# Awesome-Shield-0_6.net
KiCad netlist of a schematic drawn in EAGLE
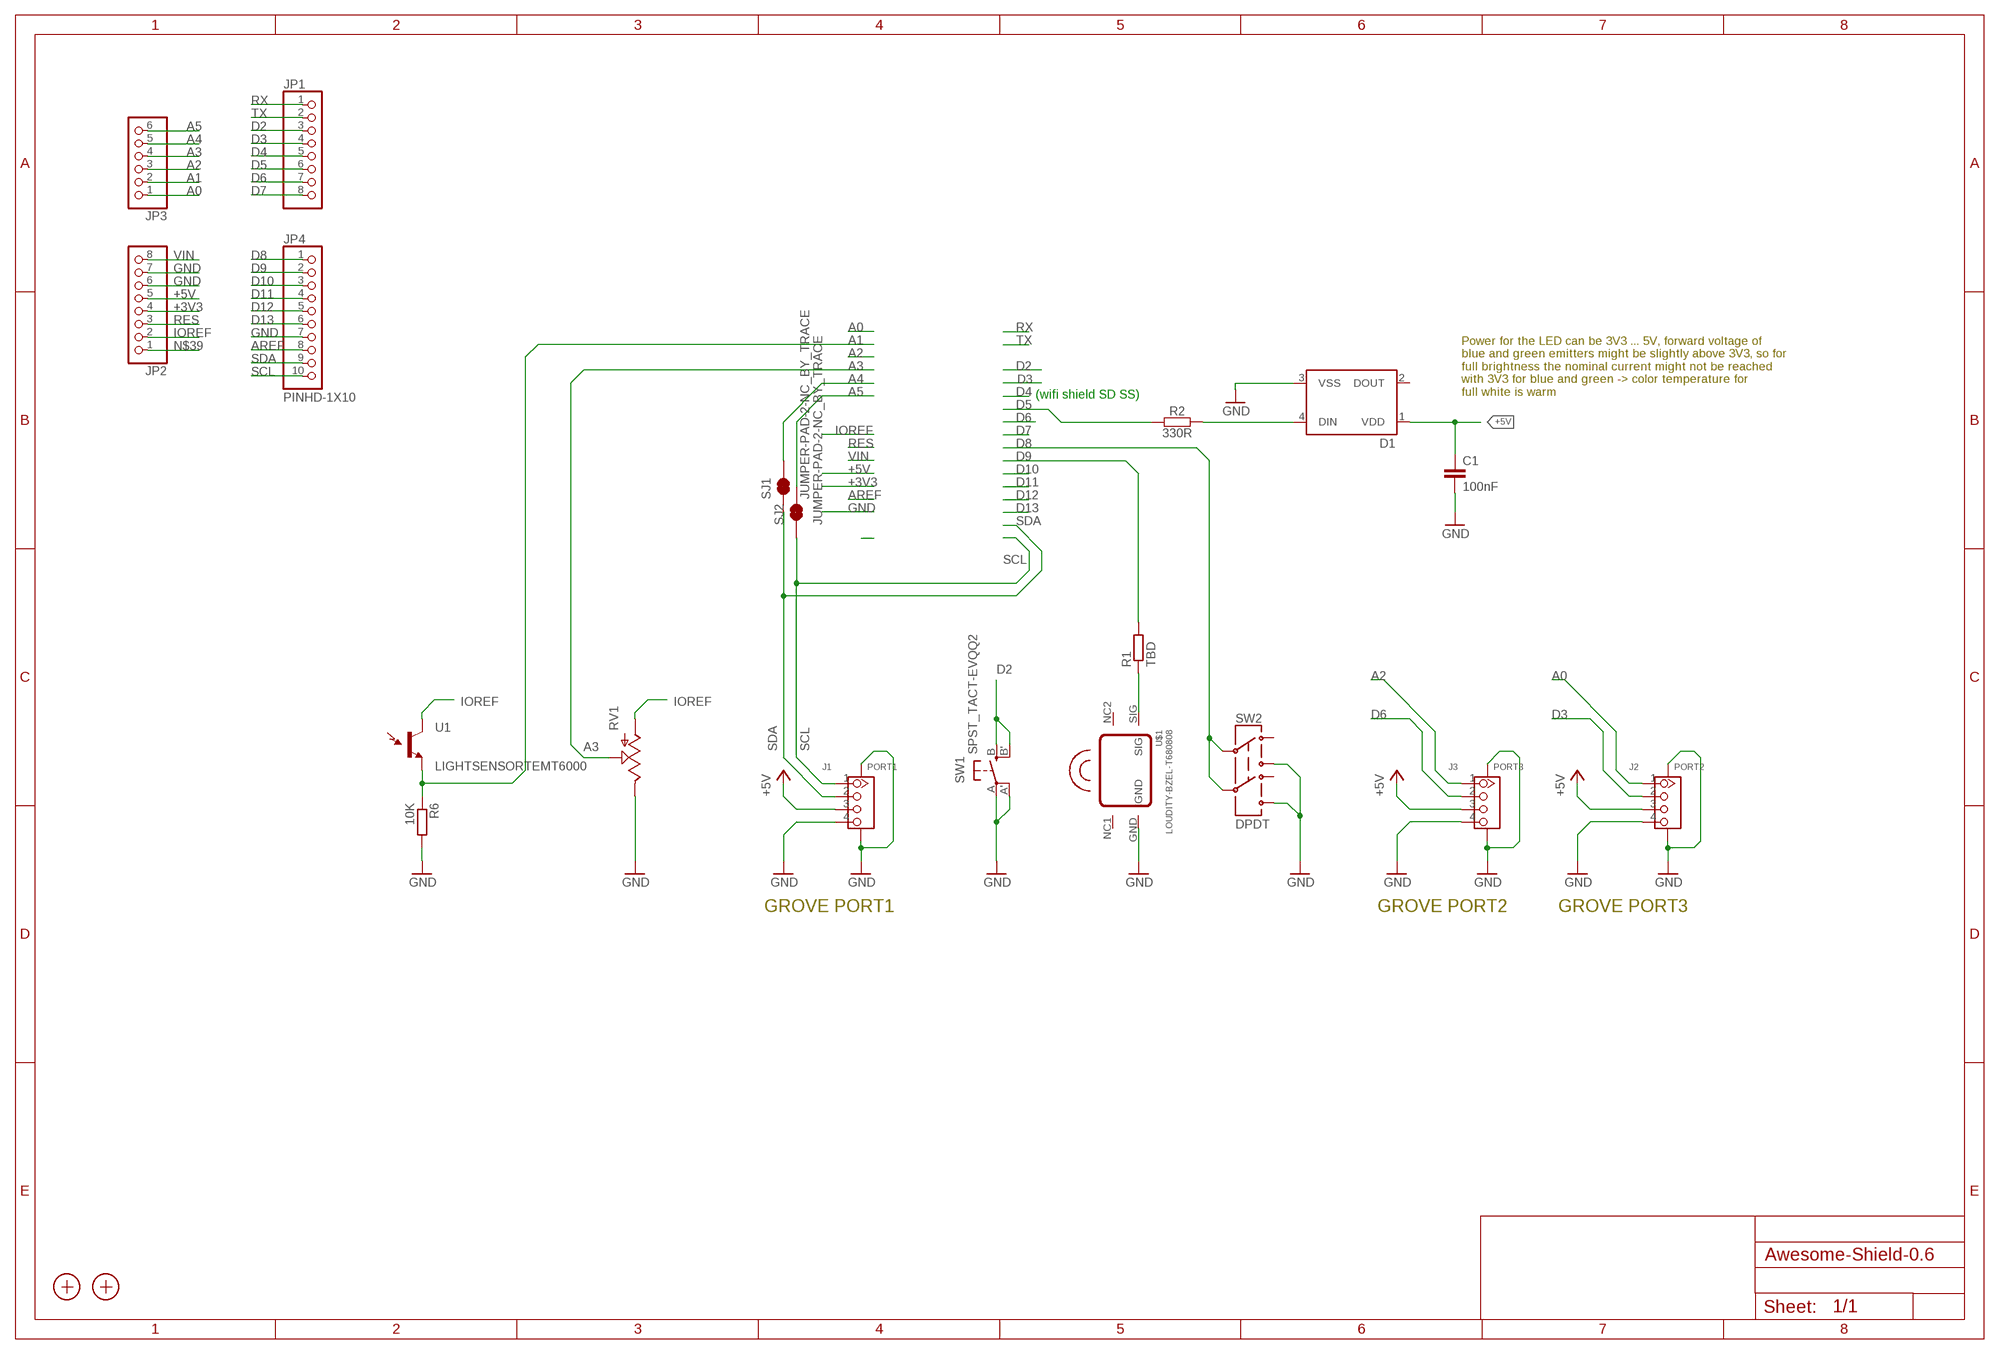
[diagram p0: schematic, sheet 1]

(export (version "E")
  (design (tool "Eeschema 10.0.6"))
  (components
    (comp (ref "C1")
      (value "100nF")
      (footprint "eagle-import:C0603")
      (libsource (lib "eagle-import") (part "C-EUC0603"))
    )
    (comp (ref "D1")
      (value "WS2812B")
      (footprint "eagle-import:WS2812B")
      (libsource (lib "eagle-import") (part "WS2812B"))
    )
    (comp (ref "J1")
      (value "PORT1")
      (footprint "eagle-import:HW4-SMD-2.0")
      (libsource (lib "eagle-import") (part "GROVE-CONNECTOR-SMD(4+2P-2.0)"))
    )
    (comp (ref "J2")
      (value "PORT2")
      (footprint "eagle-import:HW4-SMD-2.0")
      (libsource (lib "eagle-import") (part "GROVE-CONNECTOR-SMD(4+2P-2.0)"))
    )
    (comp (ref "J3")
      (value "PORT3")
      (footprint "eagle-import:HW4-SMD-2.0")
      (libsource (lib "eagle-import") (part "GROVE-CONNECTOR-SMD(4+2P-2.0)"))
    )
    (comp (ref "JP1")
      (value "PINHD-1X8CLEANBIG")
      (footprint "eagle-import:1X08-CLEANBIG")
      (libsource (lib "eagle-import") (part "PINHD-1X8CLEANBIG"))
    )
    (comp (ref "JP2")
      (value "PINHD-1X8CLEANBIG")
      (footprint "eagle-import:1X08-CLEANBIG")
      (libsource (lib "eagle-import") (part "PINHD-1X8CLEANBIG"))
    )
    (comp (ref "JP3")
      (value "PINHD-1X6CLEAN")
      (footprint "eagle-import:1X06-CLEAN")
      (libsource (lib "eagle-import") (part "PINHD-1X6CLEAN"))
    )
    (comp (ref "JP4")
      (value "PINHD-1X10")
      (footprint "eagle-import:1X10-BIG")
      (libsource (lib "eagle-import") (part "PINHD-1X10"))
    )
    (comp (ref "R1")
      (value "TBD")
      (footprint "eagle-import:R1206")
      (libsource (lib "eagle-import") (part "R-EU_R1206"))
    )
    (comp (ref "R2")
      (value "330R")
      (footprint "eagle-import:C1206")
      (libsource (lib "eagle-import") (part "RESISTOR-1206"))
    )
    (comp (ref "R6")
      (value "10K")
      (footprint "eagle-import:R1206")
      (libsource (lib "eagle-import") (part "R-EU_R1206"))
    )
    (comp (ref "RV1")
      (value "POT")
      (footprint "eagle-import:ALPS_POT")
      (libsource (lib "eagle-import") (part "POT"))
    )
    (comp (ref "SJ1")
      (value "JUMPER-PAD-2-NC_BY_TRACE")
      (footprint "eagle-import:PAD-JUMPER-2-NC_BY_TRACE_YES_SILK")
      (libsource (lib "eagle-import") (part "JUMPER-PAD-2-NC_BY_TRACE"))
    )
    (comp (ref "SJ2")
      (value "JUMPER-PAD-2-NC_BY_TRACE")
      (footprint "eagle-import:PAD-JUMPER-2-NC_BY_TRACE_YES_SILK")
      (libsource (lib "eagle-import") (part "JUMPER-PAD-2-NC_BY_TRACE"))
    )
    (comp (ref "SW1")
      (value "SPST_TACT-EVQQ2")
      (footprint "eagle-import:EVQ-Q2")
      (libsource (lib "eagle-import") (part "SPST_TACT-EVQQ2"))
    )
    (comp (ref "SW2")
      (value "DPDT")
      (footprint "eagle-import:AYZ0202")
      (libsource (lib "eagle-import") (part "SWITCH-DPDTAYZ0202"))
    )
    (comp (ref "U$1")
      (value "LOUDITY-BZEL-T680808")
      (footprint "eagle-import:SMT-68")
      (libsource (lib "eagle-import") (part "LOUDITY-BZEL-T680808"))
    )
    (comp (ref "U1")
      (value "LIGHTSENSORTEMT6000")
      (footprint "eagle-import:TEMT6000-SEN")
      (libsource (lib "eagle-import") (part "LIGHTSENSORTEMT6000"))
    )
    (comp (ref "X1")
      (value "PASSER-07")
      (footprint "eagle-import:PASSER_07MM")
      (libsource (lib "eagle-import") (part "PASSER-07"))
    )
    (comp (ref "X2")
      (value "PASSER-07")
      (footprint "eagle-import:PASSER_07MM")
      (libsource (lib "eagle-import") (part "PASSER-07"))
    )
  )
  (nets
    (net (code "1") (name "+5V") (class "Default")
      (node (ref "C1") (pin "1") (pinfunction "1_1") (pintype "passive"))
      (node (ref "D1") (pin "1") (pinfunction "VDD_1") (pintype "power_in"))
      (node (ref "J1") (pin "3") (pinfunction "3_3") (pintype "bidirectional"))
      (node (ref "J2") (pin "3") (pinfunction "3_3") (pintype "bidirectional"))
      (node (ref "J3") (pin "3") (pinfunction "3_3") (pintype "bidirectional"))
      (node (ref "JP2") (pin "5") (pinfunction "5_5") (pintype "passive"))
    )
    (net (code "2") (name "/+3V3") (class "Default")
      (node (ref "JP2") (pin "4") (pinfunction "4_4") (pintype "passive"))
    )
    (net (code "3") (name "/A0") (class "Default")
      (node (ref "J2") (pin "1") (pinfunction "1_1") (pintype "bidirectional"))
      (node (ref "JP3") (pin "1") (pinfunction "1_1") (pintype "passive"))
    )
    (net (code "4") (name "/A1") (class "Default")
      (node (ref "JP3") (pin "2") (pinfunction "2_2") (pintype "passive"))
      (node (ref "R6") (pin "1") (pinfunction "1_1") (pintype "passive"))
      (node (ref "U1") (pin "EMITTER") (pinfunction "E1_EMITTER") (pintype "passive"))
    )
    (net (code "5") (name "/A2") (class "Default")
      (node (ref "J3") (pin "1") (pinfunction "1_1") (pintype "bidirectional"))
      (node (ref "JP3") (pin "3") (pinfunction "3_3") (pintype "passive"))
    )
    (net (code "6") (name "/A3") (class "Default")
      (node (ref "JP3") (pin "4") (pinfunction "4_4") (pintype "passive"))
      (node (ref "RV1") (pin "P$2") (pinfunction "S_P$2") (pintype "passive"))
    )
    (net (code "7") (name "/A4") (class "Default")
      (node (ref "JP3") (pin "5") (pinfunction "5_5") (pintype "passive"))
      (node (ref "SJ1") (pin "2") (pinfunction "2_2") (pintype "passive"))
    )
    (net (code "8") (name "/A5") (class "Default")
      (node (ref "JP3") (pin "6") (pinfunction "6_6") (pintype "passive"))
      (node (ref "SJ2") (pin "2") (pinfunction "2_2") (pintype "passive"))
    )
    (net (code "9") (name "/AREF") (class "Default")
      (node (ref "JP4") (pin "8") (pinfunction "8_8") (pintype "passive"))
    )
    (net (code "10") (name "/D2") (class "Default")
      (node (ref "JP1") (pin "3") (pinfunction "3_3") (pintype "passive"))
      (node (ref "SW1") (pin "B") (pinfunction "S_B") (pintype "passive"))
      (node (ref "SW1") (pin "B'") (pinfunction "S1_B'") (pintype "passive"))
    )
    (net (code "11") (name "/D3") (class "Default")
      (node (ref "J2") (pin "2") (pinfunction "2_2") (pintype "bidirectional"))
      (node (ref "JP1") (pin "4") (pinfunction "4_4") (pintype "passive"))
    )
    (net (code "12") (name "/D4") (class "Default")
      (node (ref "JP1") (pin "5") (pinfunction "5_5") (pintype "passive"))
    )
    (net (code "13") (name "/D5") (class "Default")
      (node (ref "JP1") (pin "6") (pinfunction "6_6") (pintype "passive"))
      (node (ref "R2") (pin "1") (pinfunction "1_1") (pintype "passive"))
    )
    (net (code "14") (name "/D6") (class "Default")
      (node (ref "J3") (pin "2") (pinfunction "2_2") (pintype "bidirectional"))
      (node (ref "JP1") (pin "7") (pinfunction "7_7") (pintype "passive"))
    )
    (net (code "15") (name "/D7") (class "Default")
      (node (ref "JP1") (pin "8") (pinfunction "8_8") (pintype "passive"))
    )
    (net (code "16") (name "/D8") (class "Default")
      (node (ref "JP4") (pin "1") (pinfunction "1_1") (pintype "passive"))
      (node (ref "SW2") (pin "2") (pinfunction "2_2") (pintype "bidirectional"))
      (node (ref "SW2") (pin "5") (pinfunction "5_5") (pintype "bidirectional"))
    )
    (net (code "17") (name "/D9") (class "Default")
      (node (ref "JP4") (pin "2") (pinfunction "2_2") (pintype "passive"))
      (node (ref "R1") (pin "2") (pinfunction "2_2") (pintype "passive"))
    )
    (net (code "18") (name "/D10") (class "Default")
      (node (ref "JP4") (pin "3") (pinfunction "3_3") (pintype "passive"))
    )
    (net (code "19") (name "/D11") (class "Default")
      (node (ref "JP4") (pin "4") (pinfunction "4_4") (pintype "passive"))
    )
    (net (code "20") (name "/D12") (class "Default")
      (node (ref "JP4") (pin "5") (pinfunction "5_5") (pintype "passive"))
    )
    (net (code "21") (name "/D13") (class "Default")
      (node (ref "JP4") (pin "6") (pinfunction "6_6") (pintype "passive"))
    )
    (net (code "22") (name "/IOREF") (class "Default")
      (node (ref "JP2") (pin "2") (pinfunction "2_2") (pintype "passive"))
      (node (ref "RV1") (pin "P$3") (pinfunction "A_P$3") (pintype "passive"))
      (node (ref "U1") (pin "COLLECTOR") (pinfunction "C1_COLLECTOR") (pintype "passive"))
    )
    (net (code "23") (name "/N$39") (class "Default")
      (node (ref "JP2") (pin "1") (pinfunction "1_1") (pintype "passive"))
    )
    (net (code "24") (name "/RES") (class "Default")
      (node (ref "JP2") (pin "3") (pinfunction "3_3") (pintype "passive"))
    )
    (net (code "25") (name "/RX") (class "Default")
      (node (ref "JP1") (pin "1") (pinfunction "1_1") (pintype "passive"))
    )
    (net (code "26") (name "/SCL") (class "Default")
      (node (ref "J1") (pin "1") (pinfunction "1_1") (pintype "bidirectional"))
      (node (ref "JP4") (pin "10") (pinfunction "10_10") (pintype "passive"))
      (node (ref "SJ2") (pin "1") (pinfunction "1_1") (pintype "passive"))
    )
    (net (code "27") (name "/SDA") (class "Default")
      (node (ref "J1") (pin "2") (pinfunction "2_2") (pintype "bidirectional"))
      (node (ref "JP4") (pin "9") (pinfunction "9_9") (pintype "passive"))
      (node (ref "SJ1") (pin "1") (pinfunction "1_1") (pintype "passive"))
    )
    (net (code "28") (name "/TX") (class "Default")
      (node (ref "JP1") (pin "2") (pinfunction "2_2") (pintype "passive"))
    )
    (net (code "29") (name "/VIN") (class "Default")
      (node (ref "JP2") (pin "8") (pinfunction "8_8") (pintype "passive"))
    )
    (net (code "30") (name "GND") (class "Default")
      (node (ref "C1") (pin "2") (pinfunction "2_2") (pintype "passive"))
      (node (ref "D1") (pin "3") (pinfunction "VSS_3") (pintype "power_in"))
      (node (ref "J1") (pin "4") (pinfunction "4_4") (pintype "bidirectional"))
      (node (ref "J1") (pin "SS1") (pinfunction "SS1_SS1") (pintype "bidirectional"))
      (node (ref "J1") (pin "SS2") (pinfunction "SS2_SS2") (pintype "bidirectional"))
      (node (ref "J2") (pin "4") (pinfunction "4_4") (pintype "bidirectional"))
      (node (ref "J2") (pin "SS1") (pinfunction "SS1_SS1") (pintype "bidirectional"))
      (node (ref "J2") (pin "SS2") (pinfunction "SS2_SS2") (pintype "bidirectional"))
      (node (ref "J3") (pin "4") (pinfunction "4_4") (pintype "bidirectional"))
      (node (ref "J3") (pin "SS1") (pinfunction "SS1_SS1") (pintype "bidirectional"))
      (node (ref "J3") (pin "SS2") (pinfunction "SS2_SS2") (pintype "bidirectional"))
      (node (ref "JP2") (pin "6") (pinfunction "6_6") (pintype "passive"))
      (node (ref "JP2") (pin "7") (pinfunction "7_7") (pintype "passive"))
      (node (ref "JP4") (pin "7") (pinfunction "7_7") (pintype "passive"))
      (node (ref "R6") (pin "2") (pinfunction "2_2") (pintype "passive"))
      (node (ref "RV1") (pin "P$1") (pinfunction "E_P$1") (pintype "passive"))
      (node (ref "SW1") (pin "A") (pinfunction "P_A") (pintype "passive"))
      (node (ref "SW1") (pin "A'") (pinfunction "P1_A'") (pintype "passive"))
      (node (ref "SW2") (pin "3") (pinfunction "3_3") (pintype "bidirectional"))
      (node (ref "SW2") (pin "6") (pinfunction "6_6") (pintype "bidirectional"))
      (node (ref "U$1") (pin "GND") (pinfunction "GND_GND") (pintype "bidirectional"))
    )
    (net (code "31") (name "Net-(D1-DIN)") (class "Default")
      (node (ref "D1") (pin "4") (pinfunction "DIN_4") (pintype "input"))
      (node (ref "R2") (pin "2") (pinfunction "2_2") (pintype "passive"))
    )
    (net (code "32") (name "Net-(R1-Pad1)") (class "Default")
      (node (ref "R1") (pin "1") (pinfunction "1_1") (pintype "passive"))
      (node (ref "U$1") (pin "SIG") (pinfunction "SIG_SIG") (pintype "bidirectional"))
    )
    (net (code "33") (name "unconnected-(D1-DOUT-Pad2)") (class "Default")
      (node (ref "D1") (pin "2") (pinfunction "DOUT_2") (pintype "output"))
    )
    (net (code "34") (name "unconnected-(SW2-Pad1)") (class "Default")
      (node (ref "SW2") (pin "1") (pinfunction "1_1") (pintype "bidirectional"))
    )
    (net (code "35") (name "unconnected-(SW2-Pad4)") (class "Default")
      (node (ref "SW2") (pin "4") (pinfunction "4_4") (pintype "bidirectional"))
    )
    (net (code "36") (name "unconnected-(U$1-NC-PadNC1)") (class "Default")
      (node (ref "U$1") (pin "NC1") (pinfunction "NC_NC1") (pintype "bidirectional"))
    )
    (net (code "37") (name "unconnected-(U$1-NC-PadNC2)") (class "Default")
      (node (ref "U$1") (pin "NC2") (pinfunction "NC_NC2") (pintype "bidirectional"))
    )
  )
)
